# PulseDetector.net
KiCad netlist of a schematic drawn in EAGLE
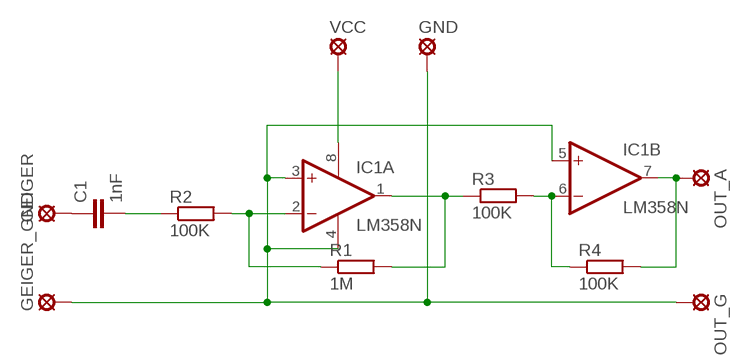
[diagram p0: schematic, sheet 1]

(export (version "E")
  (design (tool "Eeschema 10.0.6"))
  (components
    (comp (ref "C1")
      (value "1nF")
      (footprint "eagle-import:C025-025X050")
      (libsource (lib "eagle-import") (part "C-EU025-025X050"))
    )
    (comp (ref "GEIGER")
      (value "LSP10")
      (footprint "eagle-import:LSP10")
      (libsource (lib "eagle-import") (part "LSP10"))
    )
    (comp (ref "GEIGER_GND")
      (value "LSP10")
      (footprint "eagle-import:LSP10")
      (libsource (lib "eagle-import") (part "LSP10"))
    )
    (comp (ref "GND")
      (value "LSP10")
      (footprint "eagle-import:LSP10")
      (libsource (lib "eagle-import") (part "LSP10"))
    )
    (comp (ref "IC1")
      (value "LM358N")
      (footprint "eagle-import:DIL08")
      (libsource (lib "eagle-import") (part "LM358N"))
    )
    (comp (ref "OUT_A")
      (value "LSP10")
      (footprint "eagle-import:LSP10")
      (libsource (lib "eagle-import") (part "LSP10"))
    )
    (comp (ref "OUT_G")
      (value "LSP10")
      (footprint "eagle-import:LSP10")
      (libsource (lib "eagle-import") (part "LSP10"))
    )
    (comp (ref "R1")
      (value "1M")
      (footprint "eagle-import:0207_10")
      (libsource (lib "eagle-import") (part "R-EU_0207/10"))
    )
    (comp (ref "R2")
      (value "100K")
      (footprint "eagle-import:0207_10")
      (libsource (lib "eagle-import") (part "R-EU_0207/10"))
    )
    (comp (ref "R3")
      (value "100K")
      (footprint "eagle-import:0207_10")
      (libsource (lib "eagle-import") (part "R-EU_0207/10"))
    )
    (comp (ref "R4")
      (value "100K")
      (footprint "eagle-import:0207_10")
      (libsource (lib "eagle-import") (part "R-EU_0207/10"))
    )
    (comp (ref "VCC")
      (value "LSP10")
      (footprint "eagle-import:LSP10")
      (libsource (lib "eagle-import") (part "LSP10"))
    )
  )
  (nets
    (net (code "1") (name "Net-(C1-Pad1)") (class "Default")
      (node (ref "C1") (pin "1") (pinfunction "1_1") (pintype "passive"))
      (node (ref "GEIGER") (pin "MP") (pinfunction "MP_MP") (pintype "passive"))
    )
    (net (code "2") (name "Net-(C1-Pad2)") (class "Default")
      (node (ref "C1") (pin "2") (pinfunction "2_2") (pintype "passive"))
      (node (ref "R2") (pin "1") (pinfunction "1_1") (pintype "passive"))
    )
    (net (code "3") (name "Net-(IC1A-+IN)") (class "Default")
      (node (ref "GEIGER_GND") (pin "MP") (pinfunction "MP_MP") (pintype "passive"))
      (node (ref "GND") (pin "MP") (pinfunction "MP_MP") (pintype "passive"))
      (node (ref "IC1") (pin "3") (pinfunction "+IN_3") (pintype "input"))
      (node (ref "IC1") (pin "4") (pinfunction "V-_4") (pintype "power_in"))
      (node (ref "IC1") (pin "5") (pinfunction "+IN_5") (pintype "input"))
      (node (ref "OUT_G") (pin "MP") (pinfunction "MP_MP") (pintype "passive"))
    )
    (net (code "4") (name "Net-(IC1A--IN)") (class "Default")
      (node (ref "IC1") (pin "2") (pinfunction "-IN_2") (pintype "input"))
      (node (ref "R1") (pin "1") (pinfunction "1_1") (pintype "passive"))
      (node (ref "R2") (pin "2") (pinfunction "2_2") (pintype "passive"))
    )
    (net (code "5") (name "Net-(IC1A-OUT)") (class "Default")
      (node (ref "IC1") (pin "1") (pinfunction "OUT_1") (pintype "output"))
      (node (ref "R1") (pin "2") (pinfunction "2_2") (pintype "passive"))
      (node (ref "R3") (pin "1") (pinfunction "1_1") (pintype "passive"))
    )
    (net (code "6") (name "Net-(IC1B--IN)") (class "Default")
      (node (ref "IC1") (pin "6") (pinfunction "-IN_6") (pintype "input"))
      (node (ref "R3") (pin "2") (pinfunction "2_2") (pintype "passive"))
      (node (ref "R4") (pin "1") (pinfunction "1_1") (pintype "passive"))
    )
    (net (code "7") (name "Net-(IC1B-OUT)") (class "Default")
      (node (ref "IC1") (pin "7") (pinfunction "OUT_7") (pintype "output"))
      (node (ref "OUT_A") (pin "MP") (pinfunction "MP_MP") (pintype "passive"))
      (node (ref "R4") (pin "2") (pinfunction "2_2") (pintype "passive"))
    )
    (net (code "8") (name "Net-(IC1C-V+)") (class "Default")
      (node (ref "IC1") (pin "8") (pinfunction "V+_8") (pintype "power_in"))
      (node (ref "VCC") (pin "MP") (pinfunction "MP_MP") (pintype "passive"))
    )
  )
)
